# 24-BOOT_MODE_BUFFER_AND_SWITCHES.net
KiCad netlist of a schematic drawn in Altium Designer
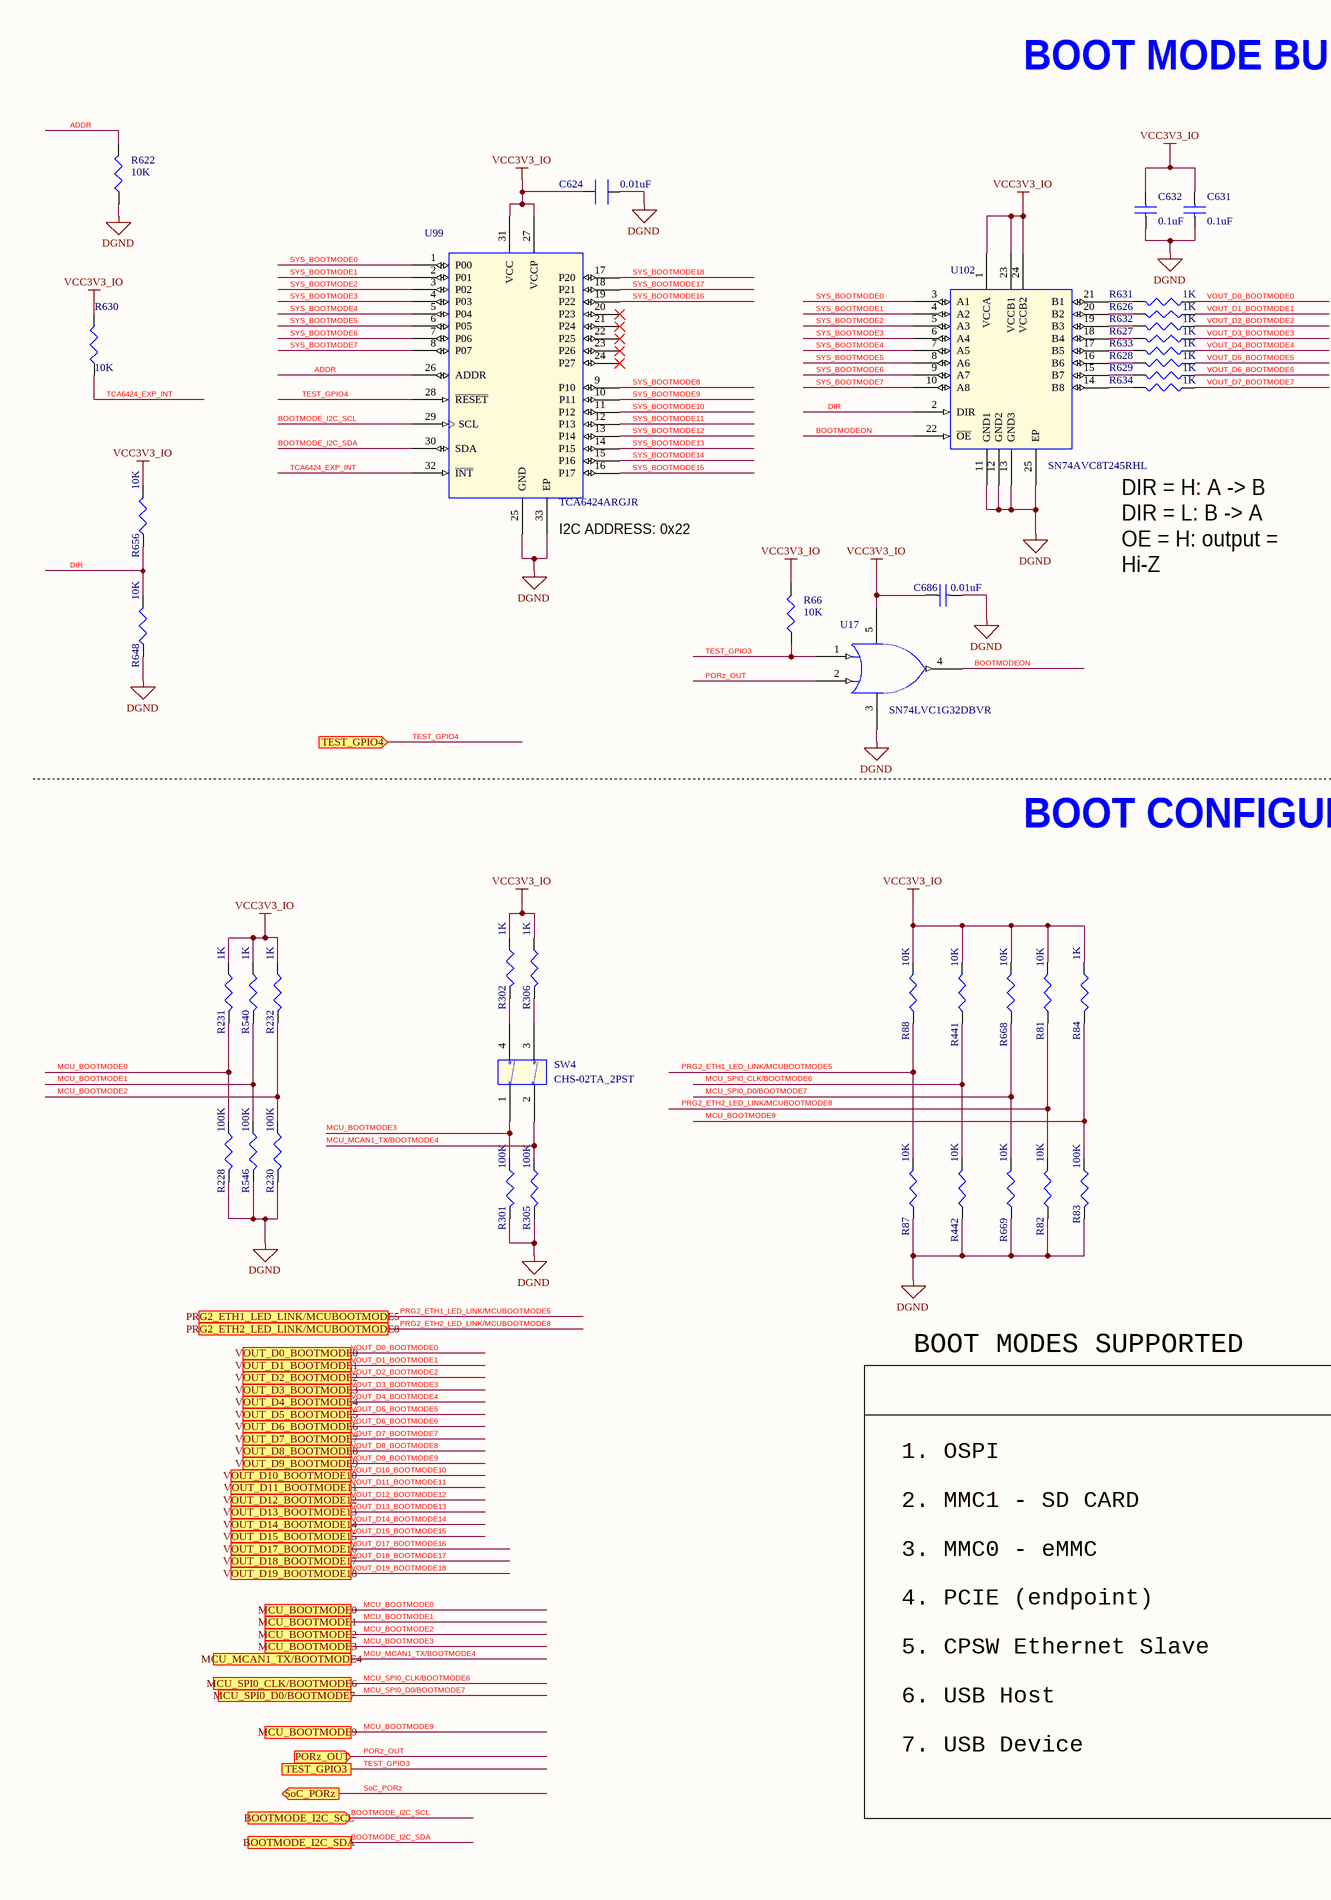
[diagram p0: 24-BOOT MODE BUFFER AND SWITCHES.SchDoc, left]
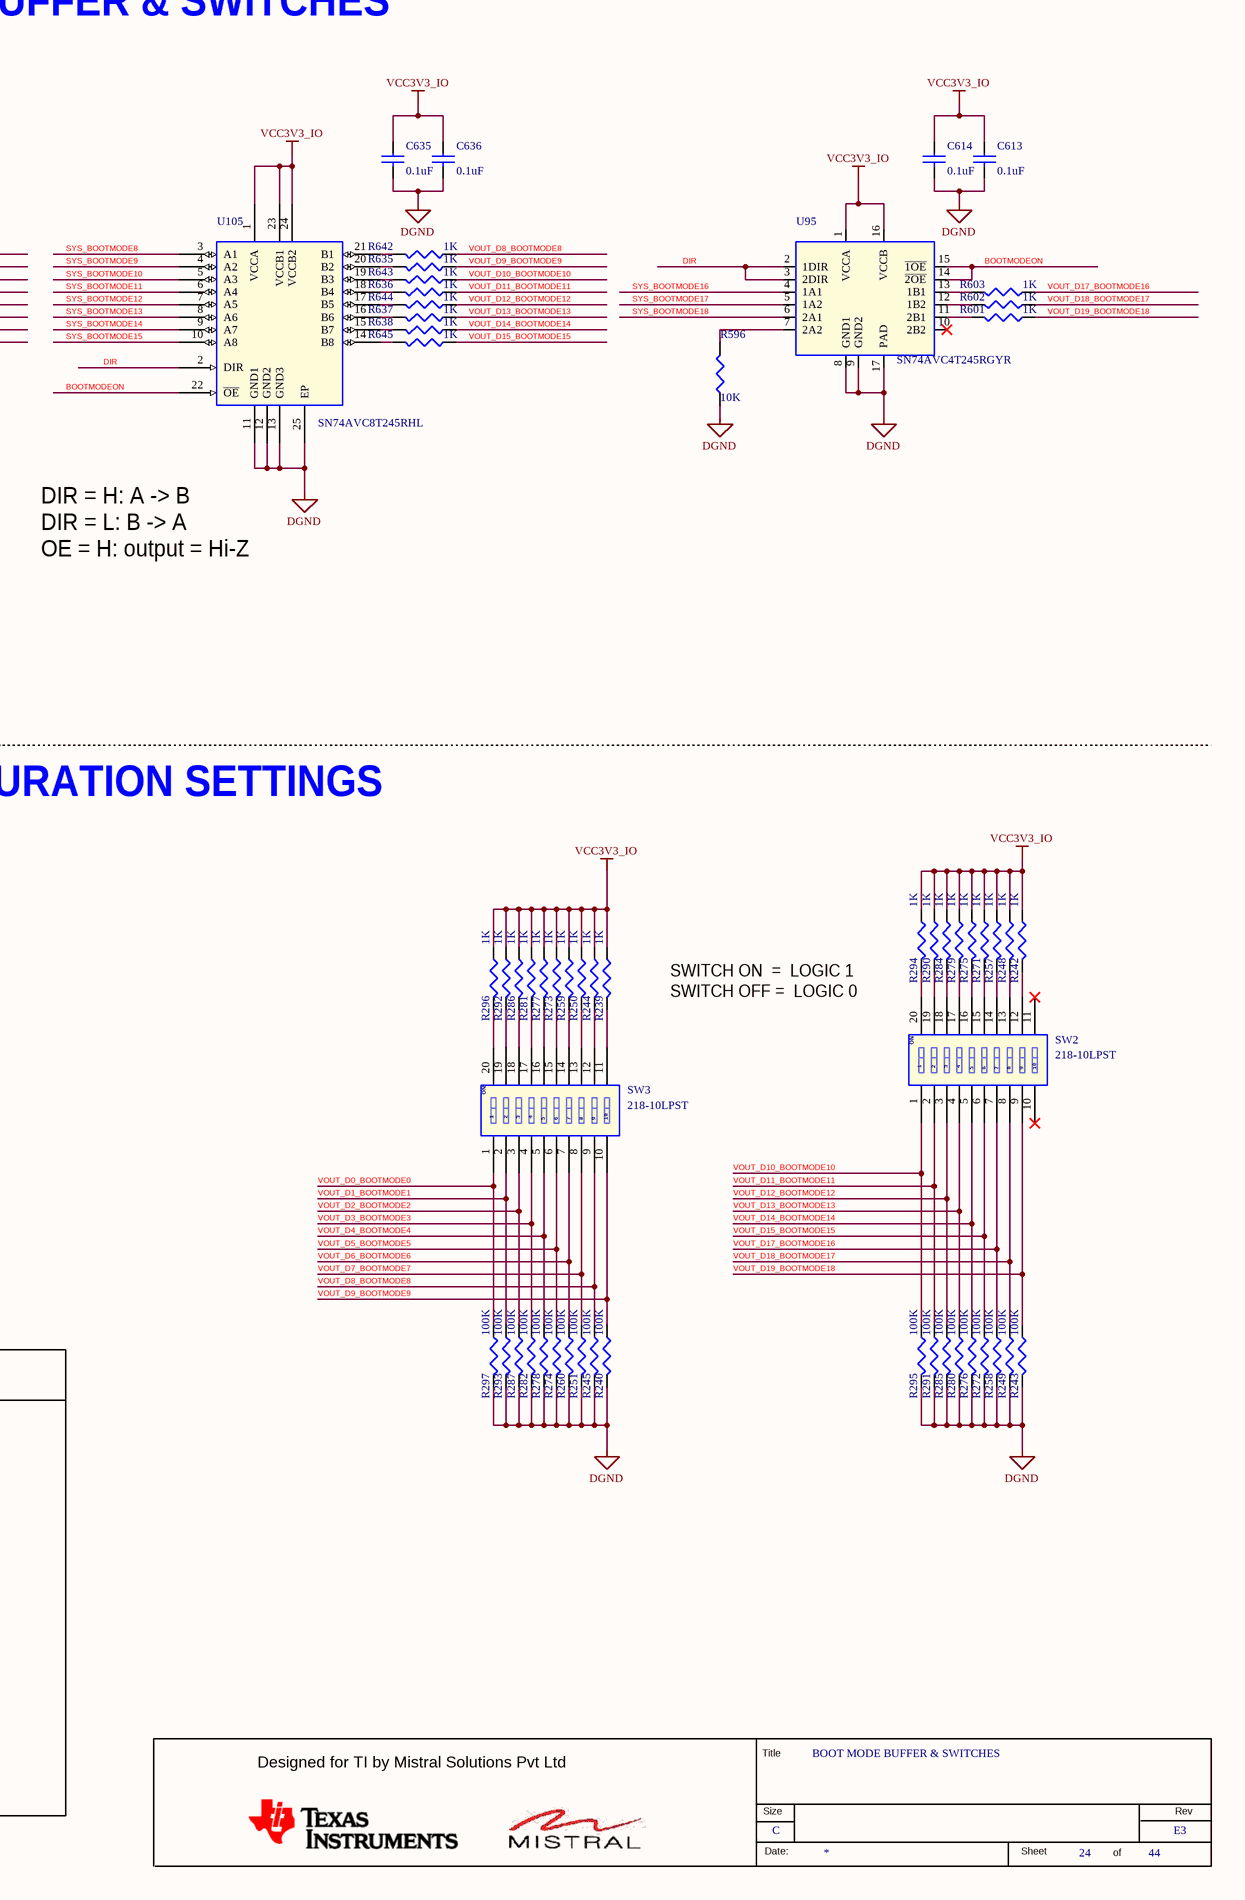
[diagram p1: 24-BOOT MODE BUFFER AND SWITCHES.SchDoc, right]

(export (version "E")
  (design (tool "Eeschema 10.0.6"))
  (components
    (comp (ref "C613")
      (value "0.1uF")
      (footprint "CAP0201_0-5")
      (description "CAP CERAMIC 0.1uF 16V 10% X5R 0201")
      (fields (field (name "DISTRIBUTOR_PART_NUMBER") "490-16742-1-ND") (field (name "VOLTAGE") "16V"))
      (libsource (lib "*") (part "CAP_Dup5"))
    )
    (comp (ref "C614")
      (value "0.1uF")
      (footprint "CAP0201_0-5")
      (description "CAP CERAMIC 0.1uF 16V 10% X5R 0201")
      (fields
        (field (name "MISTRAL PART NO") "120009030072-R")
        (field (name "MFR_PART_NUMBER") "GRM033R61C104KE84J")
      )
      (libsource (lib "*") (part "CAP_Dup5"))
    )
    (comp (ref "C624")
      (value "0.01uF")
      (footprint "TMDX654GPEVM_BRD:CAP0201_0-5")
      (description "CAP CERAMIC 0.01uF 25V 10% X5R 0201")
      (fields
        (field (name "MISTRAL PART NO") "120018010007-R")
        (field (name "MFR_PART_NUMBER") "GRM033R61E103KA12J")
      )
      (libsource (lib "*") (part "CAP_Dup3"))
    )
    (comp (ref "C631")
      (value "0.1uF")
      (footprint "CAP0201_0-5")
      (description "CAP CERAMIC 0.1uF 16V 10% X5R 0201")
      (fields
        (field (name "MISTRAL PART NO") "120009030072-R")
        (field (name "MFR_PART_NUMBER") "GRM033R61C104KE84J")
      )
      (libsource (lib "*") (part "CAP_Dup5"))
    )
    (comp (ref "C632")
      (value "0.1uF")
      (footprint "CAP0201_0-5")
      (description "CAP CERAMIC 0.1uF 16V 10% X5R 0201")
      (fields (field (name "DISTRIBUTOR_PART_NUMBER") "490-16742-1-ND") (field (name "VOLTAGE") "16V"))
      (libsource (lib "*") (part "CAP_Dup5"))
    )
    (comp (ref "C635")
      (value "0.1uF")
      (footprint "CAP0201_0-5")
      (description "CAP CERAMIC 0.1uF 16V 10% X5R 0201")
      (fields (field (name "DISTRIBUTOR_PART_NUMBER") "490-16742-1-ND") (field (name "VOLTAGE") "16V"))
      (libsource (lib "*") (part "CAP_Dup5"))
    )
    (comp (ref "C636")
      (value "0.1uF")
      (footprint "CAP0201_0-5")
      (description "CAP CERAMIC 0.1uF 16V 10% X5R 0201")
      (fields
        (field (name "MISTRAL PART NO") "120009030072-R")
        (field (name "MFR_PART_NUMBER") "GRM033R61C104KE84J")
      )
      (libsource (lib "*") (part "CAP_Dup5"))
    )
    (comp (ref "C686")
      (value "0.01uF")
      (footprint "CAP0201_0-5")
      (description "CAP CERAMIC 0.01uF 25V 10% X5R 0201")
      (fields
        (field (name "MISTRAL PART NO") "120018010007-R")
        (field (name "MFR_PART_NUMBER") "GRM033R61E103KA12J")
      )
      (libsource (lib "*") (part "CAP_Dup5"))
    )
    (comp (ref "R66")
      (value "10K")
      (footprint "RES0402_0-5")
      (description "RES 10K 1/16W 5% 0402")
      (fields (field (name "DISTRIBUTOR_PART_NUMBER") "311-10KJRCT-ND") (field (name "VOLTAGE") "NA"))
      (libsource (lib "*") (part "RESISTOR_Dup5"))
    )
    (comp (ref "R81")
      (value "10K")
      (footprint "RES0402_0-5")
      (description "RES 10K 1/16W 5% 0402")
      (fields
        (field (name "MISTRAL PART NO") "110009030208-R")
        (field (name "MFR_PART_NUMBER") "RC0402JR-0710KL")
      )
      (libsource (lib "*") (part "RESISTOR_Dup5"))
    )
    (comp (ref "R82")
      (value "10K")
      (footprint "RES0402_0-5")
      (description "RES 10K 1/16W 5% 0402")
      (fields
        (field (name "MISTRAL PART NO") "110009030208-R")
        (field (name "MFR_PART_NUMBER") "RC0402JR-0710KL")
      )
      (libsource (lib "*") (part "RESISTOR_Dup5"))
    )
    (comp (ref "R83")
      (value "100K")
      (footprint "RES0402_0-5")
      (description "RES 100K 1/16W 5% 0402")
      (fields
        (field (name "MISTRAL PART NO") "110011060002-R")
        (field (name "MFR_PART_NUMBER") "CRCW0402100KJNED")
      )
      (libsource (lib "*") (part "RESISTOR_Dup4"))
    )
    (comp (ref "R84")
      (value "1K")
      (footprint "RES0402")
      (description "RES 1K 1/16W 5% 0402")
      (fields
        (field (name "MISTRAL PART NO") "110010120017-R")
        (field (name "MFR_PART_NUMBER") "CRCW04021K00JNED")
      )
      (libsource (lib "*") (part "RESISTOR_Dup5"))
    )
    (comp (ref "R87")
      (value "10K")
      (footprint "RES0402_0-5")
      (description "RES 10K 1/16W 5% 0402")
      (fields (field (name "DISTRIBUTOR_PART_NUMBER") "311-10KJRCT-ND") (field (name "VOLTAGE") "NA"))
      (libsource (lib "*") (part "RESISTOR_Dup5"))
    )
    (comp (ref "R88")
      (value "10K")
      (footprint "RES0402_0-5")
      (description "RES 10K 1/16W 5% 0402")
      (fields
        (field (name "MISTRAL PART NO") "110009030208-R")
        (field (name "MFR_PART_NUMBER") "RC0402JR-0710KL")
      )
      (libsource (lib "*") (part "RESISTOR_Dup5"))
    )
    (comp (ref "R228")
      (value "100K")
      (footprint "RES0402_0-5")
      (description "RES 100K 1/16W 5% 0402")
      (fields
        (field (name "MISTRAL PART NO") "110011060002-R")
        (field (name "MFR_PART_NUMBER") "CRCW0402100KJNED")
      )
      (libsource (lib "*") (part "RESISTOR_Dup4"))
    )
    (comp (ref "R230")
      (value "100K")
      (footprint "RES0402_0-5")
      (description "RES 100K 1/16W 5% 0402")
      (fields
        (field (name "MISTRAL PART NO") "110011060002-R")
        (field (name "MFR_PART_NUMBER") "CRCW0402100KJNED")
      )
      (libsource (lib "*") (part "RESISTOR_Dup4"))
    )
    (comp (ref "R231")
      (value "1K")
      (footprint "RES0201")
      (description "RES 1K 1/20W 5% 0201")
      (fields (field (name "DISTRIBUTOR_PART_NUMBER") "541-1.00KAABCT-ND") (field (name "VOLTAGE") "NA"))
      (libsource (lib "*") (part "RESISTOR_Dup4"))
    )
    (comp (ref "R232")
      (value "1K")
      (footprint "RES0201")
      (description "RES 1K 1/20W 5% 0201")
      (fields
        (field (name "MISTRAL PART NO") "110015080014-R")
        (field (name "MFR_PART_NUMBER") "CRCW02011K00FKED")
      )
      (libsource (lib "*") (part "RESISTOR_Dup4"))
    )
    (comp (ref "R239")
      (value "1K")
      (footprint "RES0201")
      (description "RES 1K 1/20W 5% 0201")
      (fields
        (field (name "MISTRAL PART NO") "110015080014-R")
        (field (name "MFR_PART_NUMBER") "CRCW02011K00FKED")
      )
      (libsource (lib "*") (part "RESISTOR_Dup4"))
    )
    (comp (ref "R240")
      (value "100K")
      (footprint "RES0402_0-5")
      (description "RES 100K 1/16W 5% 0402")
      (fields
        (field (name "MISTRAL PART NO") "110011060002-R")
        (field (name "MFR_PART_NUMBER") "CRCW0402100KJNED")
      )
      (libsource (lib "*") (part "RESISTOR_Dup4"))
    )
    (comp (ref "R242")
      (value "1K")
      (footprint "RES0201")
      (description "RES 1K 1/20W 5% 0201")
      (fields (field (name "DISTRIBUTOR_PART_NUMBER") "541-1.00KAABCT-ND") (field (name "VOLTAGE") "NA"))
      (libsource (lib "*") (part "RESISTOR_Dup4"))
    )
    (comp (ref "R243")
      (value "100K")
      (footprint "RES0402_0-5")
      (description "RES 100K 1/16W 5% 0402")
      (fields (field (name "DISTRIBUTOR_PART_NUMBER") "541-100KJCT-ND") (field (name "VOLTAGE") "NA"))
      (libsource (lib "*") (part "RESISTOR_Dup4"))
    )
    (comp (ref "R244")
      (value "1K")
      (footprint "RES0201")
      (description "RES 1K 1/20W 5% 0201")
      (fields (field (name "DISTRIBUTOR_PART_NUMBER") "541-1.00KAABCT-ND") (field (name "VOLTAGE") "NA"))
      (libsource (lib "*") (part "RESISTOR_Dup4"))
    )
    (comp (ref "R245")
      (value "100K")
      (footprint "RES0402_0-5")
      (description "RES 100K 1/16W 5% 0402")
      (fields (field (name "DISTRIBUTOR_PART_NUMBER") "541-100KJCT-ND") (field (name "VOLTAGE") "NA"))
      (libsource (lib "*") (part "RESISTOR_Dup4"))
    )
    (comp (ref "R248")
      (value "1K")
      (footprint "RES0201")
      (description "RES 1K 1/20W 5% 0201")
      (fields
        (field (name "MISTRAL PART NO") "110015080014-R")
        (field (name "MFR_PART_NUMBER") "CRCW02011K00FKED")
      )
      (libsource (lib "*") (part "RESISTOR_Dup4"))
    )
    (comp (ref "R249")
      (value "100K")
      (footprint "RES0402_0-5")
      (description "RES 100K 1/16W 5% 0402")
      (fields
        (field (name "MISTRAL PART NO") "110011060002-R")
        (field (name "MFR_PART_NUMBER") "CRCW0402100KJNED")
      )
      (libsource (lib "*") (part "RESISTOR_Dup4"))
    )
    (comp (ref "R250")
      (value "1K")
      (footprint "RES0201")
      (description "RES 1K 1/20W 5% 0201")
      (fields
        (field (name "MISTRAL PART NO") "110015080014-R")
        (field (name "MFR_PART_NUMBER") "CRCW02011K00FKED")
      )
      (libsource (lib "*") (part "RESISTOR_Dup4"))
    )
    (comp (ref "R251")
      (value "100K")
      (footprint "RES0402_0-5")
      (description "RES 100K 1/16W 5% 0402")
      (fields
        (field (name "MISTRAL PART NO") "110011060002-R")
        (field (name "MFR_PART_NUMBER") "CRCW0402100KJNED")
      )
      (libsource (lib "*") (part "RESISTOR_Dup4"))
    )
    (comp (ref "R257")
      (value "1K")
      (footprint "RES0201")
      (description "RES 1K 1/20W 5% 0201")
      (fields (field (name "DISTRIBUTOR_PART_NUMBER") "541-1.00KAABCT-ND") (field (name "VOLTAGE") "NA"))
      (libsource (lib "*") (part "RESISTOR_Dup4"))
    )
    (comp (ref "R258")
      (value "100K")
      (footprint "RES0402_0-5")
      (description "RES 100K 1/16W 5% 0402")
      (fields (field (name "DISTRIBUTOR_PART_NUMBER") "541-100KJCT-ND") (field (name "VOLTAGE") "NA"))
      (libsource (lib "*") (part "RESISTOR_Dup4"))
    )
    (comp (ref "R259")
      (value "1K")
      (footprint "RES0201")
      (description "RES 1K 1/20W 5% 0201")
      (fields (field (name "DISTRIBUTOR_PART_NUMBER") "541-1.00KAABCT-ND") (field (name "VOLTAGE") "NA"))
      (libsource (lib "*") (part "RESISTOR_Dup4"))
    )
    (comp (ref "R260")
      (value "100K")
      (footprint "RES0402_0-5")
      (description "RES 100K 1/16W 5% 0402")
      (fields (field (name "DISTRIBUTOR_PART_NUMBER") "541-100KJCT-ND") (field (name "VOLTAGE") "NA"))
      (libsource (lib "*") (part "RESISTOR_Dup4"))
    )
    (comp (ref "R271")
      (value "1K")
      (footprint "RES0201")
      (description "RES 1K 1/20W 5% 0201")
      (fields
        (field (name "MISTRAL PART NO") "110015080014-R")
        (field (name "MFR_PART_NUMBER") "CRCW02011K00FKED")
      )
      (libsource (lib "*") (part "RESISTOR_Dup4"))
    )
    (comp (ref "R272")
      (value "100K")
      (footprint "RES0402_0-5")
      (description "RES 100K 1/16W 5% 0402")
      (fields
        (field (name "MISTRAL PART NO") "110011060002-R")
        (field (name "MFR_PART_NUMBER") "CRCW0402100KJNED")
      )
      (libsource (lib "*") (part "RESISTOR_Dup4"))
    )
    (comp (ref "R273")
      (value "1K")
      (footprint "RES0201")
      (description "RES 1K 1/20W 5% 0201")
      (fields
        (field (name "MISTRAL PART NO") "110015080014-R")
        (field (name "MFR_PART_NUMBER") "CRCW02011K00FKED")
      )
      (libsource (lib "*") (part "RESISTOR_Dup4"))
    )
    (comp (ref "R274")
      (value "100K")
      (footprint "RES0402_0-5")
      (description "RES 100K 1/16W 5% 0402")
      (fields
        (field (name "MISTRAL PART NO") "110011060002-R")
        (field (name "MFR_PART_NUMBER") "CRCW0402100KJNED")
      )
      (libsource (lib "*") (part "RESISTOR_Dup4"))
    )
    (comp (ref "R275")
      (value "1K")
      (footprint "RES0201")
      (description "RES 1K 1/20W 5% 0201")
      (fields (field (name "DISTRIBUTOR_PART_NUMBER") "541-1.00KAABCT-ND") (field (name "VOLTAGE") "NA"))
      (libsource (lib "*") (part "RESISTOR_Dup4"))
    )
    (comp (ref "R276")
      (value "100K")
      (footprint "RES0402_0-5")
      (description "RES 100K 1/16W 5% 0402")
      (fields (field (name "DISTRIBUTOR_PART_NUMBER") "541-100KJCT-ND") (field (name "VOLTAGE") "NA"))
      (libsource (lib "*") (part "RESISTOR_Dup4"))
    )
    (comp (ref "R277")
      (value "1K")
      (footprint "RES0201")
      (description "RES 1K 1/20W 5% 0201")
      (fields (field (name "DISTRIBUTOR_PART_NUMBER") "541-1.00KAABCT-ND") (field (name "VOLTAGE") "NA"))
      (libsource (lib "*") (part "RESISTOR_Dup4"))
    )
    (comp (ref "R278")
      (value "100K")
      (footprint "RES0402_0-5")
      (description "RES 100K 1/16W 5% 0402")
      (fields (field (name "DISTRIBUTOR_PART_NUMBER") "541-100KJCT-ND") (field (name "VOLTAGE") "NA"))
      (libsource (lib "*") (part "RESISTOR_Dup4"))
    )
    (comp (ref "R279")
      (value "1K")
      (footprint "RES0201")
      (description "RES 1K 1/20W 5% 0201")
      (fields
        (field (name "MISTRAL PART NO") "110015080014-R")
        (field (name "MFR_PART_NUMBER") "CRCW02011K00FKED")
      )
      (libsource (lib "*") (part "RESISTOR_Dup4"))
    )
    (comp (ref "R280")
      (value "100K")
      (footprint "RES0402_0-5")
      (description "RES 100K 1/16W 5% 0402")
      (fields (field (name "DISTRIBUTOR_PART_NUMBER") "541-100KJCT-ND") (field (name "VOLTAGE") "NA"))
      (libsource (lib "*") (part "RESISTOR_Dup4"))
    )
    (comp (ref "R281")
      (value "1K")
      (footprint "RES0201")
      (description "RES 1K 1/20W 5% 0201")
      (fields
        (field (name "MISTRAL PART NO") "110015080014-R")
        (field (name "MFR_PART_NUMBER") "CRCW02011K00FKED")
      )
      (libsource (lib "*") (part "RESISTOR_Dup4"))
    )
    (comp (ref "R282")
      (value "100K")
      (footprint "RES0402_0-5")
      (description "RES 100K 1/16W 5% 0402")
      (fields (field (name "DISTRIBUTOR_PART_NUMBER") "541-100KJCT-ND") (field (name "VOLTAGE") "NA"))
      (libsource (lib "*") (part "RESISTOR_Dup4"))
    )
    (comp (ref "R284")
      (value "1K")
      (footprint "RES0201")
      (description "RES 1K 1/20W 5% 0201")
      (fields (field (name "DISTRIBUTOR_PART_NUMBER") "541-1.00KAABCT-ND") (field (name "VOLTAGE") "NA"))
      (libsource (lib "*") (part "RESISTOR_Dup4"))
    )
    (comp (ref "R285")
      (value "100K")
      (footprint "RES0402_0-5")
      (description "RES 100K 1/16W 5% 0402")
      (fields
        (field (name "MISTRAL PART NO") "110011060002-R")
        (field (name "MFR_PART_NUMBER") "CRCW0402100KJNED")
      )
      (libsource (lib "*") (part "RESISTOR_Dup4"))
    )
    (comp (ref "R286")
      (value "1K")
      (footprint "RES0201")
      (description "RES 1K 1/20W 5% 0201")
      (fields (field (name "DISTRIBUTOR_PART_NUMBER") "541-1.00KAABCT-ND") (field (name "VOLTAGE") "NA"))
      (libsource (lib "*") (part "RESISTOR_Dup4"))
    )
    (comp (ref "R287")
      (value "100K")
      (footprint "RES0402_0-5")
      (description "RES 100K 1/16W 5% 0402")
      (fields
        (field (name "MISTRAL PART NO") "110011060002-R")
        (field (name "MFR_PART_NUMBER") "CRCW0402100KJNED")
      )
      (libsource (lib "*") (part "RESISTOR_Dup4"))
    )
    (comp (ref "R290")
      (value "1K")
      (footprint "RES0201")
      (description "RES 1K 1/20W 5% 0201")
      (fields
        (field (name "MISTRAL PART NO") "110015080014-R")
        (field (name "MFR_PART_NUMBER") "CRCW02011K00FKED")
      )
      (libsource (lib "*") (part "RESISTOR_Dup4"))
    )
    (comp (ref "R291")
      (value "100K")
      (footprint "RES0402_0-5")
      (description "RES 100K 1/16W 5% 0402")
      (fields (field (name "DISTRIBUTOR_PART_NUMBER") "541-100KJCT-ND") (field (name "VOLTAGE") "NA"))
      (libsource (lib "*") (part "RESISTOR_Dup4"))
    )
    (comp (ref "R292")
      (value "1K")
      (footprint "RES0201")
      (description "RES 1K 1/20W 5% 0201")
      (fields (field (name "DISTRIBUTOR_PART_NUMBER") "541-1.00KAABCT-ND") (field (name "VOLTAGE") "NA"))
      (libsource (lib "*") (part "RESISTOR_Dup4"))
    )
    (comp (ref "R293")
      (value "100K")
      (footprint "RES0402_0-5")
      (description "RES 100K 1/16W 5% 0402")
      (fields (field (name "DISTRIBUTOR_PART_NUMBER") "541-100KJCT-ND") (field (name "VOLTAGE") "NA"))
      (libsource (lib "*") (part "RESISTOR_Dup4"))
    )
    (comp (ref "R294")
      (value "1K")
      (footprint "RES0201")
      (description "RES 1K 1/20W 5% 0201")
      (fields (field (name "DISTRIBUTOR_PART_NUMBER") "541-1.00KAABCT-ND") (field (name "VOLTAGE") "NA"))
      (libsource (lib "*") (part "RESISTOR_Dup4"))
    )
    (comp (ref "R295")
      (value "100K")
      (footprint "RES0402_0-5")
      (description "RES 100K 1/16W 5% 0402")
      (fields
        (field (name "MISTRAL PART NO") "110011060002-R")
        (field (name "MFR_PART_NUMBER") "CRCW0402100KJNED")
      )
      (libsource (lib "*") (part "RESISTOR_Dup4"))
    )
    (comp (ref "R296")
      (value "1K")
      (footprint "RES0201")
      (description "RES 1K 1/20W 5% 0201")
      (fields (field (name "DISTRIBUTOR_PART_NUMBER") "541-1.00KAABCT-ND") (field (name "VOLTAGE") "NA"))
      (libsource (lib "*") (part "RESISTOR_Dup4"))
    )
    (comp (ref "R297")
      (value "100K")
      (footprint "RES0402_0-5")
      (description "RES 100K 1/16W 5% 0402")
      (fields
        (field (name "MISTRAL PART NO") "110011060002-R")
        (field (name "MFR_PART_NUMBER") "CRCW0402100KJNED")
      )
      (libsource (lib "*") (part "RESISTOR_Dup4"))
    )
    (comp (ref "R301")
      (value "100K")
      (footprint "RES0402_0-5")
      (description "RES 100K 1/16W 5% 0402")
      (fields (field (name "DISTRIBUTOR_PART_NUMBER") "541-100KJCT-ND") (field (name "VOLTAGE") "NA"))
      (libsource (lib "*") (part "RESISTOR_Dup4"))
    )
    (comp (ref "R302")
      (value "1K")
      (footprint "RES0201")
      (description "RES 1K 1/20W 5% 0201")
      (fields
        (field (name "MISTRAL PART NO") "110015080014-R")
        (field (name "MFR_PART_NUMBER") "CRCW02011K00FKED")
      )
      (libsource (lib "*") (part "RESISTOR_Dup4"))
    )
    (comp (ref "R305")
      (value "100K")
      (footprint "RES0402_0-5")
      (description "RES 100K 1/16W 5% 0402")
      (fields (field (name "DISTRIBUTOR_PART_NUMBER") "541-100KJCT-ND") (field (name "VOLTAGE") "NA"))
      (libsource (lib "*") (part "RESISTOR_Dup4"))
    )
    (comp (ref "R306")
      (value "1K")
      (footprint "RES0201")
      (description "RES 1K 1/20W 5% 0201")
      (fields
        (field (name "MISTRAL PART NO") "110015080014-R")
        (field (name "MFR_PART_NUMBER") "CRCW02011K00FKED")
      )
      (libsource (lib "*") (part "RESISTOR_Dup4"))
    )
    (comp (ref "R441")
      (value "10K")
      (footprint "RES0402_0-5")
      (description "RES 10K 1/16W 5% 0402")
      (fields (field (name "DISTRIBUTOR_PART_NUMBER") "311-10KJRCT-ND") (field (name "VOLTAGE") "NA"))
      (libsource (lib "*") (part "RESISTOR_Dup5"))
    )
    (comp (ref "R442")
      (value "10K")
      (footprint "RES0402_0-5")
      (description "RES 10K 1/16W 5% 0402")
      (fields
        (field (name "MISTRAL PART NO") "110009030208-R")
        (field (name "MFR_PART_NUMBER") "RC0402JR-0710KL")
      )
      (libsource (lib "*") (part "RESISTOR_Dup5"))
    )
    (comp (ref "R540")
      (value "1K")
      (footprint "RES0201")
      (description "RES 1K 1/20W 5% 0201")
      (fields
        (field (name "MISTRAL PART NO") "110015080014-R")
        (field (name "MFR_PART_NUMBER") "CRCW02011K00FKED")
      )
      (libsource (lib "*") (part "RESISTOR_Dup4"))
    )
    (comp (ref "R546")
      (value "100K")
      (footprint "RES0402_0-5")
      (description "RES 100K 1/16W 5% 0402")
      (fields
        (field (name "MISTRAL PART NO") "110011060002-R")
        (field (name "MFR_PART_NUMBER") "CRCW0402100KJNED")
      )
      (libsource (lib "*") (part "RESISTOR_Dup4"))
    )
    (comp (ref "R596")
      (value "10K")
      (footprint "RES0402_0-5")
      (description "RES 10K 1/16W 5% 0402")
      (fields
        (field (name "MISTRAL PART NO") "110009030208-R")
        (field (name "MFR_PART_NUMBER") "RC0402JR-0710KL")
      )
      (libsource (lib "*") (part "RESISTOR_Dup5"))
    )
    (comp (ref "R601")
      (value "1K")
      (footprint "RES0201")
      (description "RES 1K 1/20W 5% 0201")
      (fields
        (field (name "MISTRAL PART NO") "110015080014-R")
        (field (name "MFR_PART_NUMBER") "CRCW02011K00FKED")
      )
      (libsource (lib "*") (part "RESISTOR_Dup4"))
    )
    (comp (ref "R602")
      (value "1K")
      (footprint "RES0201")
      (description "RES 1K 1/20W 5% 0201")
      (fields (field (name "DISTRIBUTOR_PART_NUMBER") "541-1.00KAABCT-ND") (field (name "VOLTAGE") "NA"))
      (libsource (lib "*") (part "RESISTOR_Dup4"))
    )
    (comp (ref "R603")
      (value "1K")
      (footprint "RES0201")
      (description "RES 1K 1/20W 5% 0201")
      (fields
        (field (name "MISTRAL PART NO") "110015080014-R")
        (field (name "MFR_PART_NUMBER") "CRCW02011K00FKED")
      )
      (libsource (lib "*") (part "RESISTOR_Dup4"))
    )
    (comp (ref "R622")
      (value "10K")
      (footprint "RES0402_0-5")
      (description "RES 10K 1/16W 5% 0402")
      (fields
        (field (name "MISTRAL PART NO") "110009030208-R")
        (field (name "MFR_PART_NUMBER") "RC0402JR-0710KL")
      )
      (libsource (lib "*") (part "RESISTOR_Dup5"))
    )
    (comp (ref "R626")
      (value "1K")
      (footprint "RES0201")
      (description "RES 1K 1/20W 5% 0201")
      (fields (field (name "DISTRIBUTOR_PART_NUMBER") "541-1.00KAABCT-ND") (field (name "VOLTAGE") "NA"))
      (libsource (lib "*") (part "RESISTOR_Dup4"))
    )
    (comp (ref "R627")
      (value "1K")
      (footprint "RES0201")
      (description "RES 1K 1/20W 5% 0201")
      (fields (field (name "DISTRIBUTOR_PART_NUMBER") "541-1.00KAABCT-ND") (field (name "VOLTAGE") "NA"))
      (libsource (lib "*") (part "RESISTOR_Dup4"))
    )
    (comp (ref "R628")
      (value "1K")
      (footprint "RES0201")
      (description "RES 1K 1/20W 5% 0201")
      (fields (field (name "DISTRIBUTOR_PART_NUMBER") "541-1.00KAABCT-ND") (field (name "VOLTAGE") "NA"))
      (libsource (lib "*") (part "RESISTOR_Dup4"))
    )
    (comp (ref "R629")
      (value "1K")
      (footprint "RES0201")
      (description "RES 1K 1/20W 5% 0201")
      (fields
        (field (name "MISTRAL PART NO") "110015080014-R")
        (field (name "MFR_PART_NUMBER") "CRCW02011K00FKED")
      )
      (libsource (lib "*") (part "RESISTOR_Dup4"))
    )
    (comp (ref "R630")
      (value "10K")
      (footprint "RES0402_0-5")
      (description "RES 10K 1/16W 5% 0402")
      (fields
        (field (name "MISTRAL PART NO") "110009030208-R")
        (field (name "MFR_PART_NUMBER") "RC0402JR-0710KL")
      )
      (libsource (lib "*") (part "RESISTOR_Dup5"))
    )
    (comp (ref "R631")
      (value "1K")
      (footprint "RES0201")
      (description "RES 1K 1/20W 5% 0201")
      (fields
        (field (name "MISTRAL PART NO") "110015080014-R")
        (field (name "MFR_PART_NUMBER") "CRCW02011K00FKED")
      )
      (libsource (lib "*") (part "RESISTOR_Dup4"))
    )
    (comp (ref "R632")
      (value "1K")
      (footprint "RES0201")
      (description "RES 1K 1/20W 5% 0201")
      (fields
        (field (name "MISTRAL PART NO") "110015080014-R")
        (field (name "MFR_PART_NUMBER") "CRCW02011K00FKED")
      )
      (libsource (lib "*") (part "RESISTOR_Dup4"))
    )
    (comp (ref "R633")
      (value "1K")
      (footprint "RES0201")
      (description "RES 1K 1/20W 5% 0201")
      (fields
        (field (name "MISTRAL PART NO") "110015080014-R")
        (field (name "MFR_PART_NUMBER") "CRCW02011K00FKED")
      )
      (libsource (lib "*") (part "RESISTOR_Dup4"))
    )
    (comp (ref "R634")
      (value "1K")
      (footprint "RES0201")
      (description "RES 1K 1/20W 5% 0201")
      (fields (field (name "DISTRIBUTOR_PART_NUMBER") "541-1.00KAABCT-ND") (field (name "VOLTAGE") "NA"))
      (libsource (lib "*") (part "RESISTOR_Dup4"))
    )
    (comp (ref "R635")
      (value "1K")
      (footprint "RES0201")
      (description "RES 1K 1/20W 5% 0201")
      (fields (field (name "DISTRIBUTOR_PART_NUMBER") "541-1.00KAABCT-ND") (field (name "VOLTAGE") "NA"))
      (libsource (lib "*") (part "RESISTOR_Dup4"))
    )
    (comp (ref "R636")
      (value "1K")
      (footprint "RES0201")
      (description "RES 1K 1/20W 5% 0201")
      (fields (field (name "DISTRIBUTOR_PART_NUMBER") "541-1.00KAABCT-ND") (field (name "VOLTAGE") "NA"))
      (libsource (lib "*") (part "RESISTOR_Dup4"))
    )
    (comp (ref "R637")
      (value "1K")
      (footprint "RES0201")
      (description "RES 1K 1/20W 5% 0201")
      (fields (field (name "DISTRIBUTOR_PART_NUMBER") "541-1.00KAABCT-ND") (field (name "VOLTAGE") "NA"))
      (libsource (lib "*") (part "RESISTOR_Dup4"))
    )
    (comp (ref "R638")
      (value "1K")
      (footprint "RES0201")
      (description "RES 1K 1/20W 5% 0201")
      (fields
        (field (name "MISTRAL PART NO") "110015080014-R")
        (field (name "MFR_PART_NUMBER") "CRCW02011K00FKED")
      )
      (libsource (lib "*") (part "RESISTOR_Dup4"))
    )
    (comp (ref "R642")
      (value "1K")
      (footprint "RES0201")
      (description "RES 1K 1/20W 5% 0201")
      (fields
        (field (name "MISTRAL PART NO") "110015080014-R")
        (field (name "MFR_PART_NUMBER") "CRCW02011K00FKED")
      )
      (libsource (lib "*") (part "RESISTOR_Dup4"))
    )
    (comp (ref "R643")
      (value "1K")
      (footprint "RES0201")
      (description "RES 1K 1/20W 5% 0201")
      (fields
        (field (name "MISTRAL PART NO") "110015080014-R")
        (field (name "MFR_PART_NUMBER") "CRCW02011K00FKED")
      )
      (libsource (lib "*") (part "RESISTOR_Dup4"))
    )
    (comp (ref "R644")
      (value "1K")
      (footprint "RES0201")
      (description "RES 1K 1/20W 5% 0201")
      (fields
        (field (name "MISTRAL PART NO") "110015080014-R")
        (field (name "MFR_PART_NUMBER") "CRCW02011K00FKED")
      )
      (libsource (lib "*") (part "RESISTOR_Dup4"))
    )
    (comp (ref "R645")
      (value "1K")
      (footprint "RES0201")
      (description "RES 1K 1/20W 5% 0201")
      (fields (field (name "DISTRIBUTOR_PART_NUMBER") "541-1.00KAABCT-ND") (field (name "VOLTAGE") "NA"))
      (libsource (lib "*") (part "RESISTOR_Dup4"))
    )
    (comp (ref "R648")
      (value "10K")
      (footprint "RES0402_0-5")
      (description "RES 10K 1/16W 5% 0402")
      (fields (field (name "DISTRIBUTOR_PART_NUMBER") "311-10KJRCT-ND") (field (name "VOLTAGE") "NA"))
      (libsource (lib "*") (part "RESISTOR_Dup5"))
    )
    (comp (ref "R656")
      (value "10K")
      (footprint "RES0402_0-5")
      (description "RES 10K 1/16W 5% 0402")
      (fields
        (field (name "MISTRAL PART NO") "110009030208-R")
        (field (name "MFR_PART_NUMBER") "RC0402JR-0710KL")
      )
      (libsource (lib "*") (part "RESISTOR_Dup5"))
    )
    (comp (ref "R668")
      (value "10K")
      (footprint "RES0402_0-5")
      (description "RES 10K 1/16W 5% 0402")
      (fields (field (name "DISTRIBUTOR_PART_NUMBER") "311-10KJRCT-ND") (field (name "VOLTAGE") "NA"))
      (libsource (lib "*") (part "RESISTOR_Dup5"))
    )
    (comp (ref "R669")
      (value "10K")
      (footprint "RES0402_0-5")
      (description "RES 10K 1/16W 5% 0402")
      (fields (field (name "DISTRIBUTOR_PART_NUMBER") "311-10KJRCT-ND") (field (name "VOLTAGE") "NA"))
      (libsource (lib "*") (part "RESISTOR_Dup5"))
    )
    (comp (ref "SW2")
      (value "218-10LPST")
      (footprint "TMDX654GPEVM_BRD:SW10_50_550X230_SMD")
      (description "SWITCH DIP SPST HALF PITCH 10POS SMD")
      (fields (field (name "MISTRAL PART NO") "130016080032-R") (field (name "TOLERANCE") "NA"))
      (libsource (lib "*") (part "SW10_218-10LPST"))
    )
    (comp (ref "SW3")
      (value "218-10LPST")
      (footprint "TMDX654GPEVM_BRD:SW10_50_550X230_SMD")
      (description "SWITCH DIP SPST HALF PITCH 10POS SMD")
      (fields (field (name "DISTRIBUTOR_PART_NUMBER") "CT21810LPST-ND") (field (name "VOLTAGE") "NA"))
      (libsource (lib "*") (part "SW10_218-10LPST"))
    )
    (comp (ref "SW4")
      (value "CHS-02TA_2PST")
      (footprint "SW2_50x200_160x210_SMD")
      (description "SWITCH SLIDE 2PST SMD")
      (fields (field (name "MISTRAL PART NO") "130011120001-R") (field (name "MFR_PART_NUMBER") "CHS-02TA"))
      (libsource (lib "*") (part "SW4_CHS-02TA"))
    )
    (comp (ref "U17")
      (value "SN74LVC1G32DBVR")
      (footprint "SOT23-5_1-5")
      (description "IC SINGAL 2 INPUT POSITIVE OR GATE SOT23-5")
      (fields (field (name "MISTRAL PART NO") "141009030236-R") (field (name "TOLERANCE") "NA"))
      (libsource (lib "*") (part "SN74LVC1G32DBVR_SOT23-5"))
    )
    (comp (ref "U95")
      (value "SN74AVC4T245RGYR")
      (footprint "QFN16_19-68_160X140")
      (description "IC 4-BIT DUAL SUPPLY BUS TRANSCEIVER QFN16")
      (fields
        (field (name "MISTRAL PART NO") "141009030112-R")
        (field (name "DISTRIBUTOR_PART_NUMBER") "296-18231-1-ND")
      )
      (libsource (lib "*") (part "SN74AVC4T245RGYR_QFN16"))
    )
    (comp (ref "U99")
      (value "TCA6424ARGJR")
      (footprint "QFN32_19-68_200X200")
      (description "IC I2C I/O EXPANDER 24B UQFN32")
      (fields
        (field (name "DISTRIBUTOR_PART_NUMBER") "296-27844-1-ND")
        (field (name "MISTRAL PART NO") "141014090009-R")
      )
      (libsource (lib "*") (part "TCA6424ARGJR_QFN32"))
    )
    (comp (ref "U102")
      (value "SN74AVC8T245RHL")
      (footprint "QFN24_19-68_220X140_1")
      (description "IC BUS TRANSCEIVER 8-BIT DUAL-SUPPLY QFN24")
      (fields
        (field (name "MISTRAL PART NO") "143011040001-R")
        (field (name "MFR_PART_NUMBER") "SN74AVC8T245RHLR")
      )
      (libsource (lib "*") (part "SN74AVC8T245RHL_QFN24"))
    )
    (comp (ref "U105")
      (value "SN74AVC8T245RHL")
      (footprint "QFN24_19-68_220X140_1")
      (description "IC BUS TRANSCEIVER 8-BIT DUAL-SUPPLY QFN24")
      (fields
        (field (name "MISTRAL PART NO") "143011040001-R")
        (field (name "MFR_PART_NUMBER") "SN74AVC8T245RHLR")
      )
      (libsource (lib "*") (part "SN74AVC8T245RHL_QFN24"))
    )
  )
  (nets
    (net (code "1") (name "/ADDR") (class "Default")
      (node (ref "R622") (pin "2") (pinfunction "2_2") (pintype "passive"))
      (node (ref "U99") (pin "26") (pinfunction "ADDR_26") (pintype "bidirectional"))
    )
    (net (code "2") (name "/BOOTMODEON") (class "Default")
      (node (ref "U102") (pin "22") (pinfunction "~{OE}_22") (pintype "input"))
      (node (ref "U105") (pin "22") (pinfunction "~{OE}_22") (pintype "input"))
      (node (ref "U17") (pin "4") (pinfunction "Y_4") (pintype "output"))
      (node (ref "U95") (pin "14") (pinfunction "~{2OE}_14") (pintype "passive"))
      (node (ref "U95") (pin "15") (pinfunction "~{1OE}_15") (pintype "passive"))
    )
    (net (code "3") (name "/BOOTMODE_I2C_SCL") (class "Default")
      (node (ref "U99") (pin "29") (pinfunction "SCL_29") (pintype "input"))
    )
    (net (code "4") (name "/BOOTMODE_I2C_SDA") (class "Default")
      (node (ref "U99") (pin "30") (pinfunction "SDA_30") (pintype "bidirectional"))
    )
    (net (code "5") (name "/DIR") (class "Default")
      (node (ref "R648") (pin "2") (pinfunction "2_2") (pintype "passive"))
      (node (ref "R656") (pin "1") (pinfunction "1_1") (pintype "passive"))
      (node (ref "U102") (pin "2") (pinfunction "DIR_2") (pintype "input"))
      (node (ref "U105") (pin "2") (pinfunction "DIR_2") (pintype "input"))
      (node (ref "U95") (pin "2") (pinfunction "1DIR_2") (pintype "passive"))
      (node (ref "U95") (pin "3") (pinfunction "2DIR_3") (pintype "passive"))
    )
    (net (code "6") (name "/MCU_BOOTMODE0") (class "Default")
      (node (ref "R228") (pin "1") (pinfunction "1_1") (pintype "passive"))
      (node (ref "R231") (pin "2") (pinfunction "2_2") (pintype "passive"))
    )
    (net (code "7") (name "/MCU_BOOTMODE1") (class "Default")
      (node (ref "R540") (pin "2") (pinfunction "2_2") (pintype "passive"))
      (node (ref "R546") (pin "1") (pinfunction "1_1") (pintype "passive"))
    )
    (net (code "8") (name "/MCU_BOOTMODE2") (class "Default")
      (node (ref "R230") (pin "1") (pinfunction "1_1") (pintype "passive"))
      (node (ref "R232") (pin "2") (pinfunction "2_2") (pintype "passive"))
    )
    (net (code "9") (name "/MCU_BOOTMODE3") (class "Default")
      (node (ref "R301") (pin "1") (pinfunction "1_1") (pintype "passive"))
      (node (ref "SW4") (pin "1") (pinfunction "A1_1") (pintype "passive"))
    )
    (net (code "10") (name "/MCU_BOOTMODE9") (class "Default")
      (node (ref "R83") (pin "1") (pinfunction "1_1") (pintype "passive"))
      (node (ref "R84") (pin "2") (pinfunction "2_2") (pintype "passive"))
    )
    (net (code "11") (name "/MCU_MCAN1_TX{slash}BOOTMODE4") (class "Default")
      (node (ref "R305") (pin "1") (pinfunction "1_1") (pintype "passive"))
      (node (ref "SW4") (pin "2") (pinfunction "A2_2") (pintype "passive"))
    )
    (net (code "12") (name "/MCU_SPI0_CLK{slash}BOOTMODE6") (class "Default")
      (node (ref "R441") (pin "1") (pinfunction "1_1") (pintype "passive"))
      (node (ref "R442") (pin "2") (pinfunction "2_2") (pintype "passive"))
    )
    (net (code "13") (name "/MCU_SPI0_D0{slash}BOOTMODE7") (class "Default")
      (node (ref "R668") (pin "1") (pinfunction "1_1") (pintype "passive"))
      (node (ref "R669") (pin "2") (pinfunction "2_2") (pintype "passive"))
    )
    (net (code "14") (name "/PORz_OUT") (class "Default")
      (node (ref "U17") (pin "2") (pinfunction "B_2") (pintype "input"))
    )
    (net (code "15") (name "/PRG2_ETH1_LED_LINK{slash}MCUBOOTMODE5") (class "Default")
      (node (ref "R87") (pin "2") (pinfunction "2_2") (pintype "passive"))
      (node (ref "R88") (pin "1") (pinfunction "1_1") (pintype "passive"))
    )
    (net (code "16") (name "/PRG2_ETH2_LED_LINK{slash}MCUBOOTMODE8") (class "Default")
      (node (ref "R81") (pin "1") (pinfunction "1_1") (pintype "passive"))
      (node (ref "R82") (pin "2") (pinfunction "2_2") (pintype "passive"))
    )
    (net (code "17") (name "/SYS_BOOTMODE0") (class "Default")
      (node (ref "U102") (pin "3") (pinfunction "A1_3") (pintype "bidirectional"))
      (node (ref "U99") (pin "1") (pinfunction "P00_1") (pintype "bidirectional"))
    )
    (net (code "18") (name "/SYS_BOOTMODE1") (class "Default")
      (node (ref "U102") (pin "4") (pinfunction "A2_4") (pintype "bidirectional"))
      (node (ref "U99") (pin "2") (pinfunction "P01_2") (pintype "bidirectional"))
    )
    (net (code "19") (name "/SYS_BOOTMODE2") (class "Default")
      (node (ref "U102") (pin "5") (pinfunction "A3_5") (pintype "bidirectional"))
      (node (ref "U99") (pin "3") (pinfunction "P02_3") (pintype "bidirectional"))
    )
    (net (code "20") (name "/SYS_BOOTMODE3") (class "Default")
      (node (ref "U102") (pin "6") (pinfunction "A4_6") (pintype "bidirectional"))
      (node (ref "U99") (pin "4") (pinfunction "P03_4") (pintype "bidirectional"))
    )
    (net (code "21") (name "/SYS_BOOTMODE4") (class "Default")
      (node (ref "U102") (pin "7") (pinfunction "A5_7") (pintype "bidirectional"))
      (node (ref "U99") (pin "5") (pinfunction "P04_5") (pintype "bidirectional"))
    )
    (net (code "22") (name "/SYS_BOOTMODE5") (class "Default")
      (node (ref "U102") (pin "8") (pinfunction "A6_8") (pintype "bidirectional"))
      (node (ref "U99") (pin "6") (pinfunction "P05_6") (pintype "bidirectional"))
    )
    (net (code "23") (name "/SYS_BOOTMODE6") (class "Default")
      (node (ref "U102") (pin "9") (pinfunction "A7_9") (pintype "bidirectional"))
      (node (ref "U99") (pin "7") (pinfunction "P06_7") (pintype "bidirectional"))
    )
    (net (code "24") (name "/SYS_BOOTMODE7") (class "Default")
      (node (ref "U102") (pin "10") (pinfunction "A8_10") (pintype "bidirectional"))
      (node (ref "U99") (pin "8") (pinfunction "P07_8") (pintype "bidirectional"))
    )
    (net (code "25") (name "/SYS_BOOTMODE8") (class "Default")
      (node (ref "U105") (pin "3") (pinfunction "A1_3") (pintype "bidirectional"))
      (node (ref "U99") (pin "9") (pinfunction "P10_9") (pintype "bidirectional"))
    )
    (net (code "26") (name "/SYS_BOOTMODE9") (class "Default")
      (node (ref "U105") (pin "4") (pinfunction "A2_4") (pintype "bidirectional"))
      (node (ref "U99") (pin "10") (pinfunction "P11_10") (pintype "bidirectional"))
    )
    (net (code "27") (name "/SYS_BOOTMODE10") (class "Default")
      (node (ref "U105") (pin "5") (pinfunction "A3_5") (pintype "bidirectional"))
      (node (ref "U99") (pin "11") (pinfunction "P12_11") (pintype "bidirectional"))
    )
    (net (code "28") (name "/SYS_BOOTMODE11") (class "Default")
      (node (ref "U105") (pin "6") (pinfunction "A4_6") (pintype "bidirectional"))
      (node (ref "U99") (pin "12") (pinfunction "P13_12") (pintype "bidirectional"))
    )
    (net (code "29") (name "/SYS_BOOTMODE12") (class "Default")
      (node (ref "U105") (pin "7") (pinfunction "A5_7") (pintype "bidirectional"))
      (node (ref "U99") (pin "13") (pinfunction "P14_13") (pintype "bidirectional"))
    )
    (net (code "30") (name "/SYS_BOOTMODE13") (class "Default")
      (node (ref "U105") (pin "8") (pinfunction "A6_8") (pintype "bidirectional"))
      (node (ref "U99") (pin "14") (pinfunction "P15_14") (pintype "bidirectional"))
    )
    (net (code "31") (name "/SYS_BOOTMODE14") (class "Default")
      (node (ref "U105") (pin "9") (pinfunction "A7_9") (pintype "bidirectional"))
      (node (ref "U99") (pin "15") (pinfunction "P16_15") (pintype "bidirectional"))
    )
    (net (code "32") (name "/SYS_BOOTMODE15") (class "Default")
      (node (ref "U105") (pin "10") (pinfunction "A8_10") (pintype "bidirectional"))
      (node (ref "U99") (pin "16") (pinfunction "P17_16") (pintype "bidirectional"))
    )
    (net (code "33") (name "/SYS_BOOTMODE16") (class "Default")
      (node (ref "U95") (pin "4") (pinfunction "1A1_4") (pintype "bidirectional"))
      (node (ref "U99") (pin "19") (pinfunction "P22_19") (pintype "bidirectional"))
    )
    (net (code "34") (name "/SYS_BOOTMODE17") (class "Default")
      (node (ref "U95") (pin "5") (pinfunction "1A2_5") (pintype "bidirectional"))
      (node (ref "U99") (pin "18") (pinfunction "P21_18") (pintype "bidirectional"))
    )
    (net (code "35") (name "/SYS_BOOTMODE18") (class "Default")
      (node (ref "U95") (pin "6") (pinfunction "2A1_6") (pintype "bidirectional"))
      (node (ref "U99") (pin "17") (pinfunction "P20_17") (pintype "bidirectional"))
    )
    (net (code "37") (name "/TCA6424_EXP_INT") (class "Default")
      (node (ref "R630") (pin "1") (pinfunction "1_1") (pintype "passive"))
      (node (ref "U99") (pin "32") (pinfunction "~{INT}_32") (pintype "input"))
    )
    (net (code "38") (name "/TEST_GPIO3") (class "Default")
      (node (ref "R66") (pin "1") (pinfunction "1_1") (pintype "passive"))
      (node (ref "U17") (pin "1") (pinfunction "A_1") (pintype "input"))
    )
    (net (code "39") (name "/TEST_GPIO4") (class "Default")
      (node (ref "U99") (pin "28") (pinfunction "~{RESET}_28") (pintype "input"))
    )
    (net (code "40") (name "/VOUT_D0_BOOTMODE0") (class "Default")
      (node (ref "R297") (pin "1") (pinfunction "1_1") (pintype "passive"))
      (node (ref "R631") (pin "1") (pinfunction "1_1") (pintype "passive"))
      (node (ref "SW3") (pin "1") (pinfunction "1_1") (pintype "passive"))
    )
    (net (code "41") (name "/VOUT_D1_BOOTMODE1") (class "Default")
      (node (ref "R293") (pin "1") (pinfunction "1_1") (pintype "passive"))
      (node (ref "R626") (pin "1") (pinfunction "1_1") (pintype "passive"))
      (node (ref "SW3") (pin "2") (pinfunction "2_2") (pintype "passive"))
    )
    (net (code "42") (name "/VOUT_D2_BOOTMODE2") (class "Default")
      (node (ref "R287") (pin "1") (pinfunction "1_1") (pintype "passive"))
      (node (ref "R632") (pin "1") (pinfunction "1_1") (pintype "passive"))
      (node (ref "SW3") (pin "3") (pinfunction "3_3") (pintype "passive"))
    )
    (net (code "43") (name "/VOUT_D3_BOOTMODE3") (class "Default")
      (node (ref "R282") (pin "1") (pinfunction "1_1") (pintype "passive"))
      (node (ref "R627") (pin "1") (pinfunction "1_1") (pintype "passive"))
      (node (ref "SW3") (pin "4") (pinfunction "4_4") (pintype "passive"))
    )
    (net (code "44") (name "/VOUT_D4_BOOTMODE4") (class "Default")
      (node (ref "R278") (pin "1") (pinfunction "1_1") (pintype "passive"))
      (node (ref "R633") (pin "1") (pinfunction "1_1") (pintype "passive"))
      (node (ref "SW3") (pin "5") (pinfunction "5_5") (pintype "passive"))
    )
    (net (code "45") (name "/VOUT_D5_BOOTMODE5") (class "Default")
      (node (ref "R274") (pin "1") (pinfunction "1_1") (pintype "passive"))
      (node (ref "R628") (pin "1") (pinfunction "1_1") (pintype "passive"))
      (node (ref "SW3") (pin "6") (pinfunction "6_6") (pintype "passive"))
    )
    (net (code "46") (name "/VOUT_D6_BOOTMODE6") (class "Default")
      (node (ref "R260") (pin "1") (pinfunction "1_1") (pintype "passive"))
      (node (ref "R629") (pin "1") (pinfunction "1_1") (pintype "passive"))
      (node (ref "SW3") (pin "7") (pinfunction "7_7") (pintype "passive"))
    )
    (net (code "47") (name "/VOUT_D7_BOOTMODE7") (class "Default")
      (node (ref "R251") (pin "1") (pinfunction "1_1") (pintype "passive"))
      (node (ref "R634") (pin "1") (pinfunction "1_1") (pintype "passive"))
      (node (ref "SW3") (pin "8") (pinfunction "8_8") (pintype "passive"))
    )
    (net (code "48") (name "/VOUT_D8_BOOTMODE8") (class "Default")
      (node (ref "R245") (pin "1") (pinfunction "1_1") (pintype "passive"))
      (node (ref "R642") (pin "1") (pinfunction "1_1") (pintype "passive"))
      (node (ref "SW3") (pin "9") (pinfunction "9_9") (pintype "passive"))
    )
    (net (code "49") (name "/VOUT_D9_BOOTMODE9") (class "Default")
      (node (ref "R240") (pin "1") (pinfunction "1_1") (pintype "passive"))
      (node (ref "R635") (pin "1") (pinfunction "1_1") (pintype "passive"))
      (node (ref "SW3") (pin "10") (pinfunction "10_10") (pintype "passive"))
    )
    (net (code "50") (name "/VOUT_D10_BOOTMODE10") (class "Default")
      (node (ref "R295") (pin "1") (pinfunction "1_1") (pintype "passive"))
      (node (ref "R643") (pin "1") (pinfunction "1_1") (pintype "passive"))
      (node (ref "SW2") (pin "1") (pinfunction "1_1") (pintype "passive"))
    )
    (net (code "51") (name "/VOUT_D11_BOOTMODE11") (class "Default")
      (node (ref "R291") (pin "1") (pinfunction "1_1") (pintype "passive"))
      (node (ref "R636") (pin "1") (pinfunction "1_1") (pintype "passive"))
      (node (ref "SW2") (pin "2") (pinfunction "2_2") (pintype "passive"))
    )
    (net (code "52") (name "/VOUT_D12_BOOTMODE12") (class "Default")
      (node (ref "R285") (pin "1") (pinfunction "1_1") (pintype "passive"))
      (node (ref "R644") (pin "1") (pinfunction "1_1") (pintype "passive"))
      (node (ref "SW2") (pin "3") (pinfunction "3_3") (pintype "passive"))
    )
    (net (code "53") (name "/VOUT_D13_BOOTMODE13") (class "Default")
      (node (ref "R280") (pin "1") (pinfunction "1_1") (pintype "passive"))
      (node (ref "R637") (pin "1") (pinfunction "1_1") (pintype "passive"))
      (node (ref "SW2") (pin "4") (pinfunction "4_4") (pintype "passive"))
    )
    (net (code "54") (name "/VOUT_D14_BOOTMODE14") (class "Default")
      (node (ref "R276") (pin "1") (pinfunction "1_1") (pintype "passive"))
      (node (ref "R638") (pin "1") (pinfunction "1_1") (pintype "passive"))
      (node (ref "SW2") (pin "5") (pinfunction "5_5") (pintype "passive"))
    )
    (net (code "55") (name "/VOUT_D15_BOOTMODE15") (class "Default")
      (node (ref "R272") (pin "1") (pinfunction "1_1") (pintype "passive"))
      (node (ref "R645") (pin "1") (pinfunction "1_1") (pintype "passive"))
      (node (ref "SW2") (pin "6") (pinfunction "6_6") (pintype "passive"))
    )
    (net (code "56") (name "/VOUT_D17_BOOTMODE16") (class "Default")
      (node (ref "R258") (pin "1") (pinfunction "1_1") (pintype "passive"))
      (node (ref "R603") (pin "1") (pinfunction "1_1") (pintype "passive"))
      (node (ref "SW2") (pin "7") (pinfunction "7_7") (pintype "passive"))
    )
    (net (code "57") (name "/VOUT_D18_BOOTMODE17") (class "Default")
      (node (ref "R249") (pin "1") (pinfunction "1_1") (pintype "passive"))
      (node (ref "R602") (pin "1") (pinfunction "1_1") (pintype "passive"))
      (node (ref "SW2") (pin "8") (pinfunction "8_8") (pintype "passive"))
    )
    (net (code "58") (name "/VOUT_D19_BOOTMODE18") (class "Default")
      (node (ref "R243") (pin "1") (pinfunction "1_1") (pintype "passive"))
      (node (ref "R601") (pin "1") (pinfunction "1_1") (pintype "passive"))
      (node (ref "SW2") (pin "9") (pinfunction "9_9") (pintype "passive"))
    )
    (net (code "59") (name "DGND") (class "Default")
      (node (ref "C613") (pin "2") (pinfunction "2_2") (pintype "passive"))
      (node (ref "C614") (pin "2") (pinfunction "2_2") (pintype "passive"))
      (node (ref "C624") (pin "1") (pinfunction "1_1") (pintype "passive"))
      (node (ref "C631") (pin "2") (pinfunction "2_2") (pintype "passive"))
      (node (ref "C632") (pin "2") (pinfunction "2_2") (pintype "passive"))
      (node (ref "C635") (pin "2") (pinfunction "2_2") (pintype "passive"))
      (node (ref "C636") (pin "2") (pinfunction "2_2") (pintype "passive"))
      (node (ref "C686") (pin "2") (pinfunction "2_2") (pintype "passive"))
      (node (ref "R228") (pin "2") (pinfunction "2_2") (pintype "passive"))
      (node (ref "R230") (pin "2") (pinfunction "2_2") (pintype "passive"))
      (node (ref "R240") (pin "2") (pinfunction "2_2") (pintype "passive"))
      (node (ref "R243") (pin "2") (pinfunction "2_2") (pintype "passive"))
      (node (ref "R245") (pin "2") (pinfunction "2_2") (pintype "passive"))
      (node (ref "R249") (pin "2") (pinfunction "2_2") (pintype "passive"))
      (node (ref "R251") (pin "2") (pinfunction "2_2") (pintype "passive"))
      (node (ref "R258") (pin "2") (pinfunction "2_2") (pintype "passive"))
      (node (ref "R260") (pin "2") (pinfunction "2_2") (pintype "passive"))
      (node (ref "R272") (pin "2") (pinfunction "2_2") (pintype "passive"))
      (node (ref "R274") (pin "2") (pinfunction "2_2") (pintype "passive"))
      (node (ref "R276") (pin "2") (pinfunction "2_2") (pintype "passive"))
      (node (ref "R278") (pin "2") (pinfunction "2_2") (pintype "passive"))
      (node (ref "R280") (pin "2") (pinfunction "2_2") (pintype "passive"))
      (node (ref "R282") (pin "2") (pinfunction "2_2") (pintype "passive"))
      (node (ref "R285") (pin "2") (pinfunction "2_2") (pintype "passive"))
      (node (ref "R287") (pin "2") (pinfunction "2_2") (pintype "passive"))
      (node (ref "R291") (pin "2") (pinfunction "2_2") (pintype "passive"))
      (node (ref "R293") (pin "2") (pinfunction "2_2") (pintype "passive"))
      (node (ref "R295") (pin "2") (pinfunction "2_2") (pintype "passive"))
      (node (ref "R297") (pin "2") (pinfunction "2_2") (pintype "passive"))
      (node (ref "R301") (pin "2") (pinfunction "2_2") (pintype "passive"))
      (node (ref "R305") (pin "2") (pinfunction "2_2") (pintype "passive"))
      (node (ref "R442") (pin "1") (pinfunction "1_1") (pintype "passive"))
      (node (ref "R546") (pin "2") (pinfunction "2_2") (pintype "passive"))
      (node (ref "R596") (pin "1") (pinfunction "1_1") (pintype "passive"))
      (node (ref "R622") (pin "1") (pinfunction "1_1") (pintype "passive"))
      (node (ref "R648") (pin "1") (pinfunction "1_1") (pintype "passive"))
      (node (ref "R669") (pin "1") (pinfunction "1_1") (pintype "passive"))
      (node (ref "R82") (pin "1") (pinfunction "1_1") (pintype "passive"))
      (node (ref "R83") (pin "2") (pinfunction "2_2") (pintype "passive"))
      (node (ref "R87") (pin "1") (pinfunction "1_1") (pintype "passive"))
      (node (ref "U102") (pin "11") (pinfunction "GND1_11") (pintype "power_in"))
      (node (ref "U102") (pin "12") (pinfunction "GND2_12") (pintype "power_in"))
      (node (ref "U102") (pin "13") (pinfunction "GND3_13") (pintype "power_in"))
      (node (ref "U102") (pin "25") (pinfunction "EP_25") (pintype "power_in"))
      (node (ref "U105") (pin "11") (pinfunction "GND1_11") (pintype "power_in"))
      (node (ref "U105") (pin "12") (pinfunction "GND2_12") (pintype "power_in"))
      (node (ref "U105") (pin "13") (pinfunction "GND3_13") (pintype "power_in"))
      (node (ref "U105") (pin "25") (pinfunction "EP_25") (pintype "power_in"))
      (node (ref "U17") (pin "3") (pinfunction "GND_3") (pintype "power_in"))
      (node (ref "U95") (pin "17") (pinfunction "PAD_17") (pintype "power_in"))
      (node (ref "U95") (pin "8") (pinfunction "GND1_8") (pintype "power_in"))
      (node (ref "U95") (pin "9") (pinfunction "GND2_9") (pintype "power_in"))
      (node (ref "U99") (pin "25") (pinfunction "GND_25") (pintype "power_in"))
      (node (ref "U99") (pin "33") (pinfunction "EP_33") (pintype "power_in"))
    )
    (net (code "60") (name "Net-(R239-Pad2)") (class "Default")
      (node (ref "R239") (pin "2") (pinfunction "2_2") (pintype "passive"))
      (node (ref "SW3") (pin "11") (pinfunction "11_11") (pintype "passive"))
    )
    (net (code "61") (name "Net-(R242-Pad2)") (class "Default")
      (node (ref "R242") (pin "2") (pinfunction "2_2") (pintype "passive"))
      (node (ref "SW2") (pin "12") (pinfunction "12_12") (pintype "passive"))
    )
    (net (code "62") (name "Net-(R244-Pad2)") (class "Default")
      (node (ref "R244") (pin "2") (pinfunction "2_2") (pintype "passive"))
      (node (ref "SW3") (pin "12") (pinfunction "12_12") (pintype "passive"))
    )
    (net (code "63") (name "Net-(R248-Pad2)") (class "Default")
      (node (ref "R248") (pin "2") (pinfunction "2_2") (pintype "passive"))
      (node (ref "SW2") (pin "13") (pinfunction "13_13") (pintype "passive"))
    )
    (net (code "64") (name "Net-(R250-Pad2)") (class "Default")
      (node (ref "R250") (pin "2") (pinfunction "2_2") (pintype "passive"))
      (node (ref "SW3") (pin "13") (pinfunction "13_13") (pintype "passive"))
    )
    (net (code "65") (name "Net-(R257-Pad2)") (class "Default")
      (node (ref "R257") (pin "2") (pinfunction "2_2") (pintype "passive"))
      (node (ref "SW2") (pin "14") (pinfunction "14_14") (pintype "passive"))
    )
    (net (code "66") (name "Net-(R259-Pad2)") (class "Default")
      (node (ref "R259") (pin "2") (pinfunction "2_2") (pintype "passive"))
      (node (ref "SW3") (pin "14") (pinfunction "14_14") (pintype "passive"))
    )
    (net (code "67") (name "Net-(R271-Pad2)") (class "Default")
      (node (ref "R271") (pin "2") (pinfunction "2_2") (pintype "passive"))
      (node (ref "SW2") (pin "15") (pinfunction "15_15") (pintype "passive"))
    )
    (net (code "68") (name "Net-(R273-Pad2)") (class "Default")
      (node (ref "R273") (pin "2") (pinfunction "2_2") (pintype "passive"))
      (node (ref "SW3") (pin "15") (pinfunction "15_15") (pintype "passive"))
    )
    (net (code "69") (name "Net-(R275-Pad2)") (class "Default")
      (node (ref "R275") (pin "2") (pinfunction "2_2") (pintype "passive"))
      (node (ref "SW2") (pin "16") (pinfunction "16_16") (pintype "passive"))
    )
    (net (code "70") (name "Net-(R277-Pad2)") (class "Default")
      (node (ref "R277") (pin "2") (pinfunction "2_2") (pintype "passive"))
      (node (ref "SW3") (pin "16") (pinfunction "16_16") (pintype "passive"))
    )
    (net (code "71") (name "Net-(R279-Pad2)") (class "Default")
      (node (ref "R279") (pin "2") (pinfunction "2_2") (pintype "passive"))
      (node (ref "SW2") (pin "17") (pinfunction "17_17") (pintype "passive"))
    )
    (net (code "72") (name "Net-(R281-Pad2)") (class "Default")
      (node (ref "R281") (pin "2") (pinfunction "2_2") (pintype "passive"))
      (node (ref "SW3") (pin "17") (pinfunction "17_17") (pintype "passive"))
    )
    (net (code "73") (name "Net-(R284-Pad2)") (class "Default")
      (node (ref "R284") (pin "2") (pinfunction "2_2") (pintype "passive"))
      (node (ref "SW2") (pin "18") (pinfunction "18_18") (pintype "passive"))
    )
    (net (code "74") (name "Net-(R286-Pad2)") (class "Default")
      (node (ref "R286") (pin "2") (pinfunction "2_2") (pintype "passive"))
      (node (ref "SW3") (pin "18") (pinfunction "18_18") (pintype "passive"))
    )
    (net (code "75") (name "Net-(R290-Pad2)") (class "Default")
      (node (ref "R290") (pin "2") (pinfunction "2_2") (pintype "passive"))
      (node (ref "SW2") (pin "19") (pinfunction "19_19") (pintype "passive"))
    )
    (net (code "76") (name "Net-(R292-Pad2)") (class "Default")
      (node (ref "R292") (pin "2") (pinfunction "2_2") (pintype "passive"))
      (node (ref "SW3") (pin "19") (pinfunction "19_19") (pintype "passive"))
    )
    (net (code "77") (name "Net-(R294-Pad2)") (class "Default")
      (node (ref "R294") (pin "2") (pinfunction "2_2") (pintype "passive"))
      (node (ref "SW2") (pin "20") (pinfunction "20_20") (pintype "passive"))
    )
    (net (code "78") (name "Net-(R296-Pad2)") (class "Default")
      (node (ref "R296") (pin "2") (pinfunction "2_2") (pintype "passive"))
      (node (ref "SW3") (pin "20") (pinfunction "20_20") (pintype "passive"))
    )
    (net (code "79") (name "Net-(SW4-B1)") (class "Default")
      (node (ref "R302") (pin "2") (pinfunction "2_2") (pintype "passive"))
      (node (ref "SW4") (pin "4") (pinfunction "B1_4") (pintype "passive"))
    )
    (net (code "80") (name "Net-(SW4-B2)") (class "Default")
      (node (ref "R306") (pin "2") (pinfunction "2_2") (pintype "passive"))
      (node (ref "SW4") (pin "3") (pinfunction "B2_3") (pintype "passive"))
    )
    (net (code "81") (name "Net-(U95-1B1)") (class "Default")
      (node (ref "R603") (pin "2") (pinfunction "2_2") (pintype "passive"))
      (node (ref "U95") (pin "13") (pinfunction "1B1_13") (pintype "bidirectional"))
    )
    (net (code "82") (name "Net-(U95-1B2)") (class "Default")
      (node (ref "R602") (pin "2") (pinfunction "2_2") (pintype "passive"))
      (node (ref "U95") (pin "12") (pinfunction "1B2_12") (pintype "bidirectional"))
    )
    (net (code "83") (name "Net-(U95-2A2)") (class "Default")
      (node (ref "R596") (pin "2") (pinfunction "2_2") (pintype "passive"))
      (node (ref "U95") (pin "7") (pinfunction "2A2_7") (pintype "bidirectional"))
    )
    (net (code "84") (name "Net-(U95-2B1)") (class "Default")
      (node (ref "R601") (pin "2") (pinfunction "2_2") (pintype "passive"))
      (node (ref "U95") (pin "11") (pinfunction "2B1_11") (pintype "bidirectional"))
    )
    (net (code "85") (name "Net-(U102-B1)") (class "Default")
      (node (ref "R631") (pin "2") (pinfunction "2_2") (pintype "passive"))
      (node (ref "U102") (pin "21") (pinfunction "B1_21") (pintype "bidirectional"))
    )
    (net (code "86") (name "Net-(U102-B2)") (class "Default")
      (node (ref "R626") (pin "2") (pinfunction "2_2") (pintype "passive"))
      (node (ref "U102") (pin "20") (pinfunction "B2_20") (pintype "bidirectional"))
    )
    (net (code "87") (name "Net-(U102-B3)") (class "Default")
      (node (ref "R632") (pin "2") (pinfunction "2_2") (pintype "passive"))
      (node (ref "U102") (pin "19") (pinfunction "B3_19") (pintype "bidirectional"))
    )
    (net (code "88") (name "Net-(U102-B4)") (class "Default")
      (node (ref "R627") (pin "2") (pinfunction "2_2") (pintype "passive"))
      (node (ref "U102") (pin "18") (pinfunction "B4_18") (pintype "bidirectional"))
    )
    (net (code "89") (name "Net-(U102-B5)") (class "Default")
      (node (ref "R633") (pin "2") (pinfunction "2_2") (pintype "passive"))
      (node (ref "U102") (pin "17") (pinfunction "B5_17") (pintype "bidirectional"))
    )
    (net (code "90") (name "Net-(U102-B6)") (class "Default")
      (node (ref "R628") (pin "2") (pinfunction "2_2") (pintype "passive"))
      (node (ref "U102") (pin "16") (pinfunction "B6_16") (pintype "bidirectional"))
    )
    (net (code "91") (name "Net-(U102-B7)") (class "Default")
      (node (ref "R629") (pin "2") (pinfunction "2_2") (pintype "passive"))
      (node (ref "U102") (pin "15") (pinfunction "B7_15") (pintype "bidirectional"))
    )
    (net (code "92") (name "Net-(U102-B8)") (class "Default")
      (node (ref "R634") (pin "2") (pinfunction "2_2") (pintype "passive"))
      (node (ref "U102") (pin "14") (pinfunction "B8_14") (pintype "bidirectional"))
    )
    (net (code "93") (name "Net-(U105-B1)") (class "Default")
      (node (ref "R642") (pin "2") (pinfunction "2_2") (pintype "passive"))
      (node (ref "U105") (pin "21") (pinfunction "B1_21") (pintype "bidirectional"))
    )
    (net (code "94") (name "Net-(U105-B2)") (class "Default")
      (node (ref "R635") (pin "2") (pinfunction "2_2") (pintype "passive"))
      (node (ref "U105") (pin "20") (pinfunction "B2_20") (pintype "bidirectional"))
    )
    (net (code "95") (name "Net-(U105-B3)") (class "Default")
      (node (ref "R643") (pin "2") (pinfunction "2_2") (pintype "passive"))
      (node (ref "U105") (pin "19") (pinfunction "B3_19") (pintype "bidirectional"))
    )
    (net (code "96") (name "Net-(U105-B4)") (class "Default")
      (node (ref "R636") (pin "2") (pinfunction "2_2") (pintype "passive"))
      (node (ref "U105") (pin "18") (pinfunction "B4_18") (pintype "bidirectional"))
    )
    (net (code "97") (name "Net-(U105-B5)") (class "Default")
      (node (ref "R644") (pin "2") (pinfunction "2_2") (pintype "passive"))
      (node (ref "U105") (pin "17") (pinfunction "B5_17") (pintype "bidirectional"))
    )
    (net (code "98") (name "Net-(U105-B6)") (class "Default")
      (node (ref "R637") (pin "2") (pinfunction "2_2") (pintype "passive"))
      (node (ref "U105") (pin "16") (pinfunction "B6_16") (pintype "bidirectional"))
    )
    (net (code "99") (name "Net-(U105-B7)") (class "Default")
      (node (ref "R638") (pin "2") (pinfunction "2_2") (pintype "passive"))
      (node (ref "U105") (pin "15") (pinfunction "B7_15") (pintype "bidirectional"))
    )
    (net (code "100") (name "Net-(U105-B8)") (class "Default")
      (node (ref "R645") (pin "2") (pinfunction "2_2") (pintype "passive"))
      (node (ref "U105") (pin "14") (pinfunction "B8_14") (pintype "bidirectional"))
    )
    (net (code "101") (name "VCC3V3_IO") (class "Default")
      (node (ref "C613") (pin "1") (pinfunction "1_1") (pintype "passive"))
      (node (ref "C614") (pin "1") (pinfunction "1_1") (pintype "passive"))
      (node (ref "C624") (pin "2") (pinfunction "2_2") (pintype "passive"))
      (node (ref "C631") (pin "1") (pinfunction "1_1") (pintype "passive"))
      (node (ref "C632") (pin "1") (pinfunction "1_1") (pintype "passive"))
      (node (ref "C635") (pin "1") (pinfunction "1_1") (pintype "passive"))
      (node (ref "C636") (pin "1") (pinfunction "1_1") (pintype "passive"))
      (node (ref "C686") (pin "1") (pinfunction "1_1") (pintype "passive"))
      (node (ref "R231") (pin "1") (pinfunction "1_1") (pintype "passive"))
      (node (ref "R232") (pin "1") (pinfunction "1_1") (pintype "passive"))
      (node (ref "R239") (pin "1") (pinfunction "1_1") (pintype "passive"))
      (node (ref "R242") (pin "1") (pinfunction "1_1") (pintype "passive"))
      (node (ref "R244") (pin "1") (pinfunction "1_1") (pintype "passive"))
      (node (ref "R248") (pin "1") (pinfunction "1_1") (pintype "passive"))
      (node (ref "R250") (pin "1") (pinfunction "1_1") (pintype "passive"))
      (node (ref "R257") (pin "1") (pinfunction "1_1") (pintype "passive"))
      (node (ref "R259") (pin "1") (pinfunction "1_1") (pintype "passive"))
      (node (ref "R271") (pin "1") (pinfunction "1_1") (pintype "passive"))
      (node (ref "R273") (pin "1") (pinfunction "1_1") (pintype "passive"))
      (node (ref "R275") (pin "1") (pinfunction "1_1") (pintype "passive"))
      (node (ref "R277") (pin "1") (pinfunction "1_1") (pintype "passive"))
      (node (ref "R279") (pin "1") (pinfunction "1_1") (pintype "passive"))
      (node (ref "R281") (pin "1") (pinfunction "1_1") (pintype "passive"))
      (node (ref "R284") (pin "1") (pinfunction "1_1") (pintype "passive"))
      (node (ref "R286") (pin "1") (pinfunction "1_1") (pintype "passive"))
      (node (ref "R290") (pin "1") (pinfunction "1_1") (pintype "passive"))
      (node (ref "R292") (pin "1") (pinfunction "1_1") (pintype "passive"))
      (node (ref "R294") (pin "1") (pinfunction "1_1") (pintype "passive"))
      (node (ref "R296") (pin "1") (pinfunction "1_1") (pintype "passive"))
      (node (ref "R302") (pin "1") (pinfunction "1_1") (pintype "passive"))
      (node (ref "R306") (pin "1") (pinfunction "1_1") (pintype "passive"))
      (node (ref "R441") (pin "2") (pinfunction "2_2") (pintype "passive"))
      (node (ref "R540") (pin "1") (pinfunction "1_1") (pintype "passive"))
      (node (ref "R630") (pin "2") (pinfunction "2_2") (pintype "passive"))
      (node (ref "R656") (pin "2") (pinfunction "2_2") (pintype "passive"))
      (node (ref "R66") (pin "2") (pinfunction "2_2") (pintype "passive"))
      (node (ref "R668") (pin "2") (pinfunction "2_2") (pintype "passive"))
      (node (ref "R81") (pin "2") (pinfunction "2_2") (pintype "passive"))
      (node (ref "R84") (pin "1") (pinfunction "1_1") (pintype "passive"))
      (node (ref "R88") (pin "2") (pinfunction "2_2") (pintype "passive"))
      (node (ref "U102") (pin "1") (pinfunction "VCCA_1") (pintype "power_in"))
      (node (ref "U102") (pin "23") (pinfunction "VCCB1_23") (pintype "power_in"))
      (node (ref "U102") (pin "24") (pinfunction "VCCB2_24") (pintype "power_in"))
      (node (ref "U105") (pin "1") (pinfunction "VCCA_1") (pintype "power_in"))
      (node (ref "U105") (pin "23") (pinfunction "VCCB1_23") (pintype "power_in"))
      (node (ref "U105") (pin "24") (pinfunction "VCCB2_24") (pintype "power_in"))
      (node (ref "U17") (pin "5") (pinfunction "VCC_5") (pintype "power_in"))
      (node (ref "U95") (pin "1") (pinfunction "VCCA_1") (pintype "power_in"))
      (node (ref "U95") (pin "16") (pinfunction "VCCB_16") (pintype "power_in"))
      (node (ref "U99") (pin "27") (pinfunction "VCCP_27") (pintype "power_in"))
      (node (ref "U99") (pin "31") (pinfunction "VCC_31") (pintype "power_in"))
    )
    (net (code "102") (name "unconnected-(SW2-Pad10)") (class "Default")
      (node (ref "SW2") (pin "10") (pinfunction "10_10") (pintype "passive+no_connect"))
    )
    (net (code "103") (name "unconnected-(SW2-Pad11)") (class "Default")
      (node (ref "SW2") (pin "11") (pinfunction "11_11") (pintype "passive+no_connect"))
    )
    (net (code "104") (name "unconnected-(U95-2B2-Pad10)") (class "Default")
      (node (ref "U95") (pin "10") (pinfunction "2B2_10") (pintype "bidirectional+no_connect"))
    )
    (net (code "105") (name "unconnected-(U99-P23-Pad20)") (class "Default")
      (node (ref "U99") (pin "20") (pinfunction "P23_20") (pintype "bidirectional+no_connect"))
    )
    (net (code "106") (name "unconnected-(U99-P24-Pad21)") (class "Default")
      (node (ref "U99") (pin "21") (pinfunction "P24_21") (pintype "bidirectional+no_connect"))
    )
    (net (code "107") (name "unconnected-(U99-P25-Pad22)") (class "Default")
      (node (ref "U99") (pin "22") (pinfunction "P25_22") (pintype "bidirectional+no_connect"))
    )
    (net (code "108") (name "unconnected-(U99-P26-Pad23)") (class "Default")
      (node (ref "U99") (pin "23") (pinfunction "P26_23") (pintype "bidirectional+no_connect"))
    )
    (net (code "109") (name "unconnected-(U99-P27-Pad24)") (class "Default")
      (node (ref "U99") (pin "24") (pinfunction "P27_24") (pintype "bidirectional+no_connect"))
    )
  )
)
